# Schema.net
KiCad netlist of a schematic drawn in EAGLE
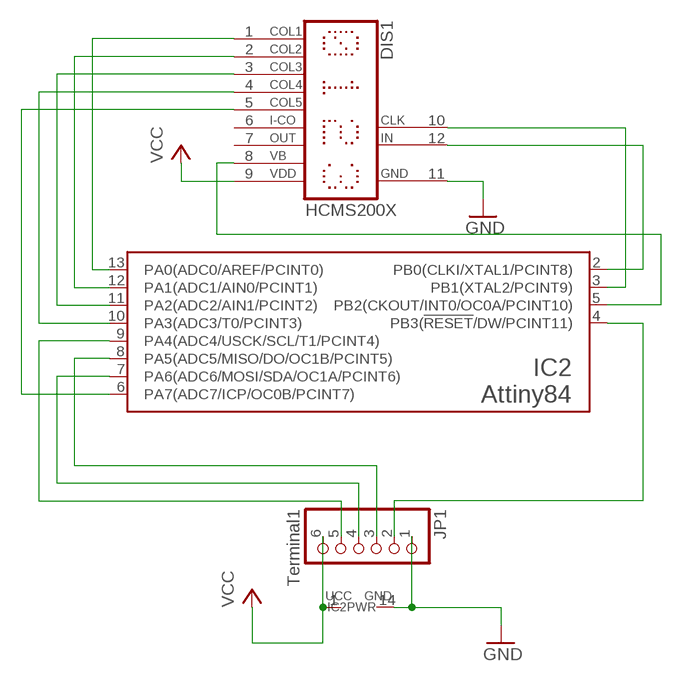
[diagram p0: schematic, sheet 1]

(export (version "E")
  (design (tool "Eeschema 10.0.6"))
  (components
    (comp (ref "DIS1")
      (value "HCMS200X")
      (footprint "eagle-import:HCMS200X")
      (libsource (lib "eagle-import") (part "HCMS200X"))
    )
    (comp (ref "IC2")
      (value "Attiny84")
      (footprint "eagle-import:DIL14")
      (libsource (lib "eagle-import") (part "ATTINY24/44/84-PU"))
    )
    (comp (ref "JP1")
      (value "Terminal1")
      (footprint "eagle-import:1X06")
      (libsource (lib "eagle-import") (part "PINHD-1X6"))
    )
  )
  (nets
    (net (code "1") (name "GND") (class "Default")
      (node (ref "DIS1") (pin "11") (pinfunction "GND_11") (pintype "power_in"))
      (node (ref "IC2") (pin "14") (pinfunction "GND_14") (pintype "power_in"))
      (node (ref "JP1") (pin "1") (pinfunction "1_1") (pintype "passive"))
    )
    (net (code "2") (name "Net-(DIS1-CLK)") (class "Default")
      (node (ref "DIS1") (pin "10") (pinfunction "CLK_10") (pintype "input"))
      (node (ref "IC2") (pin "3") (pinfunction "PB1(XTAL2/PCINT9)_3") (pintype "bidirectional"))
    )
    (net (code "3") (name "Net-(DIS1-COL1)") (class "Default")
      (node (ref "DIS1") (pin "1") (pinfunction "COL1_1") (pintype "input"))
      (node (ref "IC2") (pin "13") (pinfunction "PA0(ADC0/AREF/PCINT0)_13") (pintype "bidirectional"))
    )
    (net (code "4") (name "Net-(DIS1-COL2)") (class "Default")
      (node (ref "DIS1") (pin "2") (pinfunction "COL2_2") (pintype "input"))
      (node (ref "IC2") (pin "12") (pinfunction "PA1(ADC1/AIN0/PCINT1)_12") (pintype "bidirectional"))
    )
    (net (code "5") (name "Net-(DIS1-COL3)") (class "Default")
      (node (ref "DIS1") (pin "3") (pinfunction "COL3_3") (pintype "input"))
      (node (ref "IC2") (pin "11") (pinfunction "PA2(ADC2/AIN1/PCINT2)_11") (pintype "bidirectional"))
    )
    (net (code "6") (name "Net-(DIS1-COL4)") (class "Default")
      (node (ref "DIS1") (pin "4") (pinfunction "COL4_4") (pintype "input"))
      (node (ref "IC2") (pin "10") (pinfunction "PA3(ADC3/T0/PCINT3)_10") (pintype "bidirectional"))
    )
    (net (code "7") (name "Net-(DIS1-COL5)") (class "Default")
      (node (ref "DIS1") (pin "5") (pinfunction "COL5_5") (pintype "input"))
      (node (ref "IC2") (pin "6") (pinfunction "PA7(ADC7/ICP/OC0B/PCINT7)_6") (pintype "bidirectional"))
    )
    (net (code "8") (name "Net-(DIS1-IN)") (class "Default")
      (node (ref "DIS1") (pin "12") (pinfunction "IN_12") (pintype "input"))
      (node (ref "IC2") (pin "2") (pinfunction "PB0(CLKI/XTAL1/PCINT8)_2") (pintype "bidirectional"))
    )
    (net (code "9") (name "Net-(DIS1-VB)") (class "Default")
      (node (ref "DIS1") (pin "8") (pinfunction "VB_8") (pintype "input"))
      (node (ref "IC2") (pin "5") (pinfunction "PB2(CKOUT/INT0/OC0A/PCINT10)_5") (pintype "bidirectional"))
    )
    (net (code "10") (name "Net-(IC2A-PA4(ADC4{slash}USCK{slash}SCL{slash}T1{slash}PCINT4))") (class "Default")
      (node (ref "IC2") (pin "9") (pinfunction "PA4(ADC4/USCK/SCL/T1/PCINT4)_9") (pintype "bidirectional"))
      (node (ref "JP1") (pin "5") (pinfunction "5_5") (pintype "passive"))
    )
    (net (code "11") (name "Net-(IC2A-PA5(ADC5{slash}MISO{slash}DO{slash}OC1B{slash}PCINT5))") (class "Default")
      (node (ref "IC2") (pin "8") (pinfunction "PA5(ADC5/MISO/DO/OC1B/PCINT5)_8") (pintype "bidirectional"))
      (node (ref "JP1") (pin "3") (pinfunction "3_3") (pintype "passive"))
    )
    (net (code "12") (name "Net-(IC2A-PA6(ADC6{slash}MOSI{slash}SDA{slash}OC1A{slash}PCINT6))") (class "Default")
      (node (ref "IC2") (pin "7") (pinfunction "PA6(ADC6/MOSI/SDA/OC1A/PCINT6)_7") (pintype "bidirectional"))
      (node (ref "JP1") (pin "4") (pinfunction "4_4") (pintype "passive"))
    )
    (net (code "13") (name "Net-(IC2A-PB3(~{RESET}{slash}DW{slash}PCINT11))") (class "Default")
      (node (ref "IC2") (pin "4") (pinfunction "PB3(~{RESET}/DW/PCINT11)_4") (pintype "bidirectional"))
      (node (ref "JP1") (pin "2") (pinfunction "2_2") (pintype "passive"))
    )
    (net (code "14") (name "VCC") (class "Default")
      (node (ref "DIS1") (pin "9") (pinfunction "VDD_9") (pintype "power_in"))
      (node (ref "IC2") (pin "1") (pinfunction "UCC_1") (pintype "power_in"))
      (node (ref "JP1") (pin "6") (pinfunction "6_6") (pintype "passive"))
    )
    (net (code "15") (name "unconnected-(DIS1-I-CO-Pad6)") (class "Default")
      (node (ref "DIS1") (pin "6") (pinfunction "I-CO_6") (pintype "input"))
    )
    (net (code "16") (name "unconnected-(DIS1-OUT-Pad7)") (class "Default")
      (node (ref "DIS1") (pin "7") (pinfunction "OUT_7") (pintype "input"))
    )
  )
)
